# Controller.net
KiCad netlist of a schematic drawn in Altium Designer
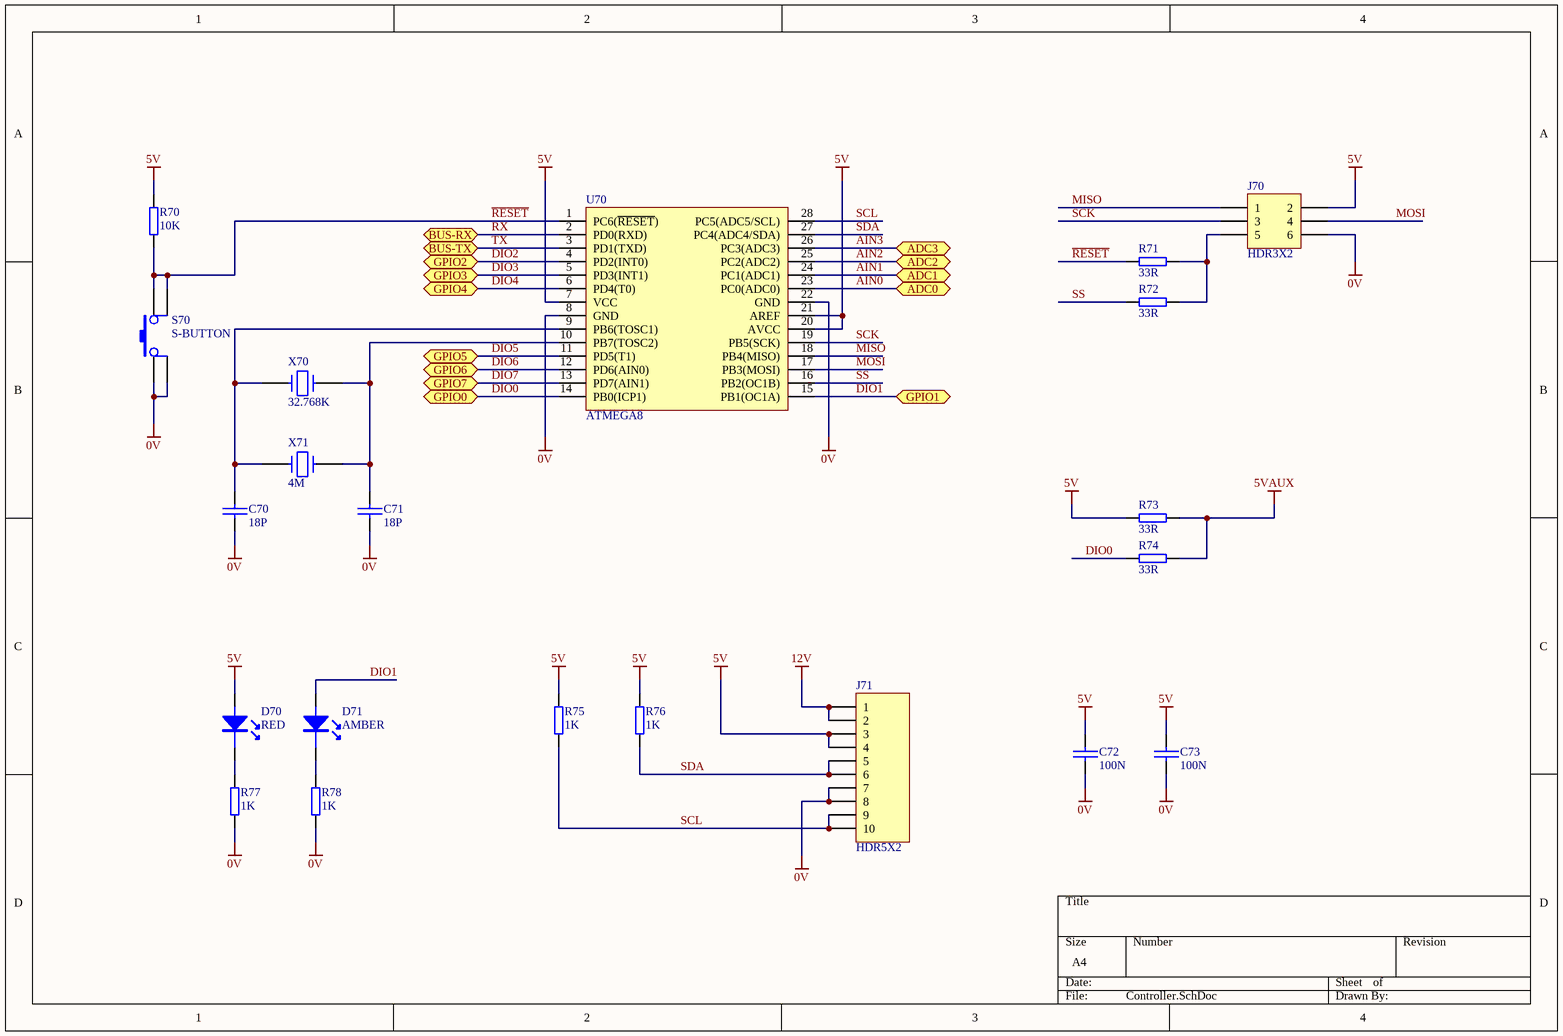
[diagram p0: Controller.SchDoc]

(export (version "E")
  (design (tool "Eeschema 10.0.6"))
  (components
    (comp (ref "C70")
      (value "18P")
      (footprint "AXIAL02")
      (description "CAPACITOR")
      (libsource (lib "SSR") (part "C-B18P"))
    )
    (comp (ref "C71")
      (value "18P")
      (footprint "AXIAL02")
      (description "CAPACITOR")
      (libsource (lib "SSR") (part "C-B18P"))
    )
    (comp (ref "C72")
      (value "100N")
      (footprint "AXIAL02")
      (description "CAPACITOR")
      (libsource (lib "SSR") (part "C-B100N"))
    )
    (comp (ref "C73")
      (value "100N")
      (footprint "AXIAL02")
      (description "CAPACITOR")
      (libsource (lib "SSR") (part "C-B100N"))
    )
    (comp (ref "D70")
      (value "RED")
      (footprint "LED5MM")
      (description "LED")
      (libsource (lib "SSR") (part "O-RED"))
    )
    (comp (ref "D71")
      (value "AMBER")
      (footprint "LED5MM")
      (description "LED")
      (libsource (lib "SSR") (part "O-AMBER"))
    )
    (comp (ref "J70")
      (value "HDR3X2")
      (footprint "HDR3X2")
      (description "CONNECTOR")
      (libsource (lib "SSR") (part "J-HDR3X2"))
    )
    (comp (ref "J71")
      (value "HDR5X2")
      (footprint "HDR5X2")
      (description "CONNECTOR")
      (libsource (lib "SSR") (part "J-HDR5X2A"))
    )
    (comp (ref "R70")
      (value "10K")
      (footprint "AXIAL04")
      (description "RESISTOR")
      (libsource (lib "SSR") (part "R-A10K"))
    )
    (comp (ref "R71")
      (value "33R")
      (footprint "AXIAL04")
      (description "RESISTOR")
      (libsource (lib "SSR") (part "R-A33R"))
    )
    (comp (ref "R72")
      (value "33R")
      (footprint "AXIAL04")
      (description "RESISTOR")
      (libsource (lib "SSR") (part "R-A33R"))
    )
    (comp (ref "R73")
      (value "33R")
      (footprint "AXIAL04")
      (description "RESISTOR")
      (libsource (lib "SSR") (part "R-A33R"))
    )
    (comp (ref "R74")
      (value "33R")
      (footprint "AXIAL04")
      (description "RESISTOR")
      (libsource (lib "SSR") (part "R-A33R"))
    )
    (comp (ref "R75")
      (value "1K")
      (footprint "AXIAL04")
      (description "RESISTOR")
      (libsource (lib "SSR") (part "R-A1K"))
    )
    (comp (ref "R76")
      (value "1K")
      (footprint "AXIAL04")
      (description "RESISTOR")
      (libsource (lib "SSR") (part "R-A1K"))
    )
    (comp (ref "R77")
      (value "1K")
      (footprint "AXIAL04")
      (description "RESISTOR")
      (libsource (lib "SSR") (part "R-A1K"))
    )
    (comp (ref "R78")
      (value "1K")
      (footprint "AXIAL04")
      (description "RESISTOR")
      (libsource (lib "SSR") (part "R-A1K"))
    )
    (comp (ref "S70")
      (value "S-BUTTON")
      (footprint "SWPB")
      (description "PUSH BUTTON SWITCH")
      (libsource (lib "SSR") (part "S-BUTTON"))
    )
    (comp (ref "U70")
      (value "ATMEGA8")
      (footprint "DIP28N")
      (description "MICROCONTROLLER")
      (libsource (lib "SSR") (part "U-ATMEGA8"))
    )
    (comp (ref "X70")
      (value "32.768K")
      (footprint "RADIAL01")
      (description "CRYSTAL")
      (libsource (lib "SSR") (part "X-32K768"))
    )
    (comp (ref "X71")
      (value "4M")
      (footprint "HC49")
      (description "CRYSTAL")
      (libsource (lib "SSR") (part "X-4M"))
    )
  )
  (nets
    (net (code "1") (name "/AIN0") (class "Default")
      (node (ref "U70") (pin "23") (pinfunction "PC0(ADC0)_23") (pintype "passive"))
    )
    (net (code "2") (name "/AIN1") (class "Default")
      (node (ref "U70") (pin "24") (pinfunction "PC1(ADC1)_24") (pintype "passive"))
    )
    (net (code "3") (name "/AIN2") (class "Default")
      (node (ref "U70") (pin "25") (pinfunction "PC2(ADC2)_25") (pintype "passive"))
    )
    (net (code "4") (name "/AIN3") (class "Default")
      (node (ref "U70") (pin "26") (pinfunction "PC3(ADC3)_26") (pintype "passive"))
    )
    (net (code "5") (name "/DIO0") (class "Default")
      (node (ref "R74") (pin "2") (pinfunction "2_2") (pintype "passive"))
      (node (ref "U70") (pin "14") (pinfunction "PB0(ICP1)_14") (pintype "passive"))
    )
    (net (code "6") (name "/DIO1") (class "Default")
      (node (ref "D71") (pin "1") (pinfunction "A_1") (pintype "passive"))
      (node (ref "U70") (pin "15") (pinfunction "PB1(OC1A)_15") (pintype "passive"))
    )
    (net (code "7") (name "/DIO2") (class "Default")
      (node (ref "U70") (pin "4") (pinfunction "PD2(INT0)_4") (pintype "passive"))
    )
    (net (code "8") (name "/DIO3") (class "Default")
      (node (ref "U70") (pin "5") (pinfunction "PD3(INT1)_5") (pintype "power_in"))
    )
    (net (code "9") (name "/DIO4") (class "Default")
      (node (ref "U70") (pin "6") (pinfunction "PD4(T0)_6") (pintype "power_in"))
    )
    (net (code "10") (name "/DIO5") (class "Default")
      (node (ref "U70") (pin "11") (pinfunction "PD5(T1)_11") (pintype "passive"))
    )
    (net (code "11") (name "/DIO6") (class "Default")
      (node (ref "U70") (pin "12") (pinfunction "PD6(AIN0)_12") (pintype "passive"))
    )
    (net (code "12") (name "/DIO7") (class "Default")
      (node (ref "U70") (pin "13") (pinfunction "PD7(AIN1)_13") (pintype "passive"))
    )
    (net (code "13") (name "/MISO") (class "Default")
      (node (ref "J70") (pin "1") (pinfunction "1_1") (pintype "passive"))
      (node (ref "U70") (pin "18") (pinfunction "PB4(MISO)_18") (pintype "passive"))
    )
    (net (code "14") (name "/MOSI") (class "Default")
      (node (ref "J70") (pin "4") (pinfunction "4_4") (pintype "passive"))
      (node (ref "U70") (pin "17") (pinfunction "PB3(MOSI)_17") (pintype "passive"))
    )
    (net (code "15") (name "/RX") (class "Default")
      (node (ref "U70") (pin "2") (pinfunction "PD0(RXD)_2") (pintype "passive"))
    )
    (net (code "16") (name "/SCK") (class "Default")
      (node (ref "J70") (pin "3") (pinfunction "3_3") (pintype "passive"))
      (node (ref "U70") (pin "19") (pinfunction "PB5(SCK)_19") (pintype "passive"))
    )
    (net (code "17") (name "/SCL") (class "Default")
      (node (ref "J71") (pin "10") (pinfunction "10_10") (pintype "passive"))
      (node (ref "J71") (pin "9") (pinfunction "9_9") (pintype "passive"))
      (node (ref "R75") (pin "1") (pinfunction "1_1") (pintype "passive"))
      (node (ref "U70") (pin "28") (pinfunction "PC5(ADC5/SCL)_28") (pintype "passive"))
    )
    (net (code "18") (name "/SDA") (class "Default")
      (node (ref "J71") (pin "5") (pinfunction "5_5") (pintype "passive"))
      (node (ref "J71") (pin "6") (pinfunction "6_6") (pintype "passive"))
      (node (ref "R76") (pin "1") (pinfunction "1_1") (pintype "passive"))
      (node (ref "U70") (pin "27") (pinfunction "PC4(ADC4/SDA)_27") (pintype "passive"))
    )
    (net (code "19") (name "/SS") (class "Default")
      (node (ref "R72") (pin "1") (pinfunction "1_1") (pintype "passive"))
      (node (ref "U70") (pin "16") (pinfunction "PB2(OC1B)_16") (pintype "passive"))
    )
    (net (code "20") (name "/TX") (class "Default")
      (node (ref "U70") (pin "3") (pinfunction "PD1(TXD)_3") (pintype "passive"))
    )
    (net (code "21") (name "/~{RESET}") (class "Default")
      (node (ref "R70") (pin "1") (pinfunction "1_1") (pintype "passive"))
      (node (ref "R71") (pin "1") (pinfunction "1_1") (pintype "passive"))
      (node (ref "S70") (pin "2") (pinfunction "2_2") (pintype "passive"))
      (node (ref "S70") (pin "4") (pinfunction "4_4") (pintype "passive"))
      (node (ref "U70") (pin "1") (pinfunction "PC6(~{RESET})_1") (pintype "passive"))
    )
    (net (code "22") (name "0V") (class "Default")
      (node (ref "C70") (pin "2") (pinfunction "2_2") (pintype "passive"))
      (node (ref "C71") (pin "2") (pinfunction "2_2") (pintype "passive"))
      (node (ref "C72") (pin "2") (pinfunction "2_2") (pintype "passive"))
      (node (ref "C73") (pin "2") (pinfunction "2_2") (pintype "passive"))
      (node (ref "J70") (pin "6") (pinfunction "6_6") (pintype "passive"))
      (node (ref "J71") (pin "7") (pinfunction "7_7") (pintype "passive"))
      (node (ref "J71") (pin "8") (pinfunction "8_8") (pintype "passive"))
      (node (ref "R77") (pin "1") (pinfunction "1_1") (pintype "passive"))
      (node (ref "R78") (pin "1") (pinfunction "1_1") (pintype "passive"))
      (node (ref "S70") (pin "1") (pinfunction "1_1") (pintype "passive"))
      (node (ref "S70") (pin "3") (pinfunction "3_3") (pintype "passive"))
      (node (ref "U70") (pin "22") (pinfunction "GND_22") (pintype "passive"))
      (node (ref "U70") (pin "8") (pinfunction "GND_8") (pintype "passive"))
    )
    (net (code "23") (name "5V") (class "Default")
      (node (ref "C72") (pin "1") (pinfunction "1_1") (pintype "passive"))
      (node (ref "C73") (pin "1") (pinfunction "1_1") (pintype "passive"))
      (node (ref "D70") (pin "1") (pinfunction "A_1") (pintype "passive"))
      (node (ref "J70") (pin "2") (pinfunction "2_2") (pintype "passive"))
      (node (ref "J71") (pin "3") (pinfunction "3_3") (pintype "passive"))
      (node (ref "J71") (pin "4") (pinfunction "4_4") (pintype "passive"))
      (node (ref "R70") (pin "2") (pinfunction "2_2") (pintype "passive"))
      (node (ref "R73") (pin "2") (pinfunction "2_2") (pintype "passive"))
      (node (ref "R75") (pin "2") (pinfunction "2_2") (pintype "passive"))
      (node (ref "R76") (pin "2") (pinfunction "2_2") (pintype "passive"))
      (node (ref "U70") (pin "20") (pinfunction "AVCC_20") (pintype "passive"))
      (node (ref "U70") (pin "21") (pinfunction "AREF_21") (pintype "passive"))
      (node (ref "U70") (pin "7") (pinfunction "VCC_7") (pintype "passive"))
    )
    (net (code "24") (name "5VAUX") (class "Default")
      (node (ref "R73") (pin "1") (pinfunction "1_1") (pintype "passive"))
      (node (ref "R74") (pin "1") (pinfunction "1_1") (pintype "passive"))
    )
    (net (code "25") (name "12V") (class "Default")
      (node (ref "J71") (pin "1") (pinfunction "1_1") (pintype "passive"))
      (node (ref "J71") (pin "2") (pinfunction "2_2") (pintype "passive"))
    )
    (net (code "26") (name "Net-(D70-K)") (class "Default")
      (node (ref "D70") (pin "2") (pinfunction "K_2") (pintype "passive"))
      (node (ref "R77") (pin "2") (pinfunction "2_2") (pintype "passive"))
    )
    (net (code "27") (name "Net-(D71-K)") (class "Default")
      (node (ref "D71") (pin "2") (pinfunction "K_2") (pintype "passive"))
      (node (ref "R78") (pin "2") (pinfunction "2_2") (pintype "passive"))
    )
    (net (code "28") (name "Net-(J70-Pad5)") (class "Default")
      (node (ref "J70") (pin "5") (pinfunction "5_5") (pintype "passive"))
      (node (ref "R71") (pin "2") (pinfunction "2_2") (pintype "passive"))
      (node (ref "R72") (pin "2") (pinfunction "2_2") (pintype "passive"))
    )
    (net (code "29") (name "Net-(U70-PB6(TOSC1))") (class "Default")
      (node (ref "C70") (pin "1") (pinfunction "1_1") (pintype "passive"))
      (node (ref "U70") (pin "9") (pinfunction "PB6(TOSC1)_9") (pintype "passive"))
      (node (ref "X70") (pin "1") (pinfunction "1_1") (pintype "passive"))
      (node (ref "X71") (pin "1") (pinfunction "1_1") (pintype "passive"))
    )
    (net (code "30") (name "Net-(U70-PB7(TOSC2))") (class "Default")
      (node (ref "C71") (pin "1") (pinfunction "1_1") (pintype "passive"))
      (node (ref "U70") (pin "10") (pinfunction "PB7(TOSC2)_10") (pintype "passive"))
      (node (ref "X70") (pin "2") (pinfunction "2_2") (pintype "passive"))
      (node (ref "X71") (pin "2") (pinfunction "2_2") (pintype "passive"))
    )
  )
)
